# RTU_LMG_CAN.net
KiCad netlist of a schematic drawn in Altium Designer
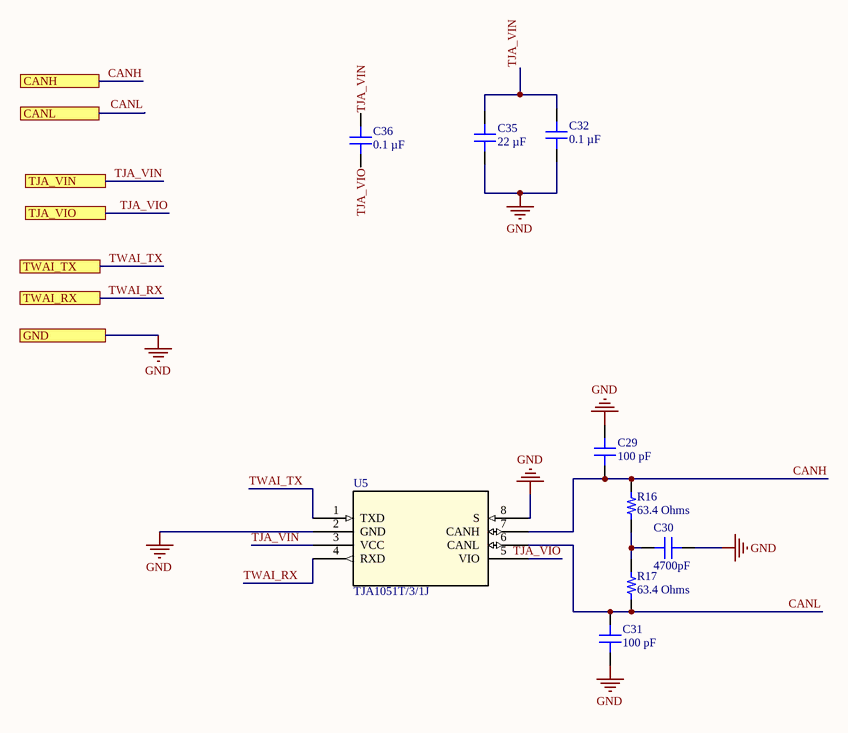
[diagram p0: RTU_LMG_CAN.SchDoc]

(export (version "E")
  (design (tool "Eeschema 10.0.6"))
  (components
    (comp (ref "C29")
      (value "100 pF")
      (footprint "CAP 0402_1005")
      (description "CAP CER 100PF 50V C0G/NP0 0402")
      (fields
        (field (name "PART NUMBER") "500X07N101MV4T")
        (field (name "CAPACITANCE") "100 pF")
        (field (name "MANUFACTURER") "Johanson Dielectrics Inc.")
      )
      (libsource (lib "Celestial Altium Library - altium_library") (part "Capacitor"))
    )
    (comp (ref "C30")
      (value "4700pF")
      (footprint "CAP 0402_1005")
      (description "CAP CER 4700PF 50V X7R 0402")
      (fields
        (field (name "PART NUMBER") "04025C472KAT2A")
        (field (name "CAPACITANCE") "4700pF")
        (field (name "MANUFACTURER") "AVX Corporation")
      )
      (libsource (lib "Celestial Altium Library - altium_library") (part "Capacitor"))
    )
    (comp (ref "C31")
      (value "100 pF")
      (footprint "CAP 0402_1005")
      (description "CAP CER 100PF 50V C0G/NP0 0402")
      (fields
        (field (name "PART NUMBER") "500X07N101MV4T")
        (field (name "CAPACITANCE") "100 pF")
        (field (name "MANUFACTURER") "Johanson Dielectrics Inc.")
      )
      (libsource (lib "Celestial Altium Library - altium_library") (part "Capacitor"))
    )
    (comp (ref "C32")
      (value "0.1 µF")
      (footprint "CAP 0402_1005")
      (description "CAP CER 0.1UF 50V X5R 0402")
      (fields
        (field (name "PART NUMBER") "CGA2B3X5R1H104M050BB")
        (field (name "CAPACITANCE") "0.1 µF")
        (field (name "MANUFACTURER") "TDK Corporation")
      )
      (libsource (lib "Celestial Altium Library - altium_library") (part "Capacitor"))
    )
    (comp (ref "C35")
      (value "22 µF")
      (footprint "CAP 0805_2012")
      (description "CAP CER 22UF 16V X5R 0805")
      (fields
        (field (name "PART NUMBER") "CL21A226MOCLRNC")
        (field (name "MANUFACTURER") "Samsung Electro-Mechanics")
      )
      (libsource (lib "Celestial Altium Library - altium_library") (part "Capacitor"))
    )
    (comp (ref "C36")
      (value "0.1 µF")
      (footprint "CAP 0402_1005")
      (description "CAP CER 0.1UF 50V X5R 0402")
      (fields
        (field (name "PART NUMBER") "CGA2B3X5R1H104M050BB")
        (field (name "CAPACITANCE") "0.1 µF")
        (field (name "MANUFACTURER") "TDK Corporation")
      )
      (libsource (lib "Celestial Altium Library - altium_library") (part "Capacitor"))
    )
    (comp (ref "R16")
      (value "63.4 Ohms")
      (footprint "RES 0805_2012")
      (description "RES SMD 63.4 OHM 1% 1/8W 0805")
      (fields
        (field (name "PART NUMBER") "ERJ-6ENF63R4V")
        (field (name "MANUFACTURER") "Panasonic Electronic Components")
      )
      (libsource (lib "Celestial Altium Library - altium_library") (part "Resistor"))
    )
    (comp (ref "R17")
      (value "63.4 Ohms")
      (footprint "RES 0805_2012")
      (description "RES SMD 63.4 OHM 1% 1/8W 0805")
      (fields
        (field (name "PART NUMBER") "ERJ-6ENF63R4V")
        (field (name "MANUFACTURER") "Panasonic Electronic Components")
      )
      (libsource (lib "Celestial Altium Library - altium_library") (part "Resistor"))
    )
    (comp (ref "U5")
      (value "TJA1051T/3/1J")
      (footprint "SO8_SOT96-1_NXP")
      (description "Description")
      (fields (field (name "COPYRIGHT") "Copyright (C) 2025 Ultra Librarian. All rights reserved."))
      (libsource (lib "TJA1051T31J") (part "TJA1051T31J"))
    )
  )
  (nets
    (net (code "1") (name "/CANH") (class "Default")
      (node (ref "C29") (pin "1") (pinfunction "1_1") (pintype "passive"))
      (node (ref "R16") (pin "2") (pinfunction "2_2") (pintype "passive"))
      (node (ref "U5") (pin "7") (pinfunction "CANH_7") (pintype "bidirectional"))
    )
    (net (code "2") (name "/CANL") (class "Default")
      (node (ref "C31") (pin "2") (pinfunction "2_2") (pintype "passive"))
      (node (ref "R17") (pin "1") (pinfunction "1_1") (pintype "passive"))
      (node (ref "U5") (pin "6") (pinfunction "CANL_6") (pintype "bidirectional"))
    )
    (net (code "3") (name "/TJA_VIN") (class "Default")
      (node (ref "C32") (pin "1") (pinfunction "1_1") (pintype "passive"))
      (node (ref "C35") (pin "2") (pinfunction "2_2") (pintype "passive"))
      (node (ref "C36") (pin "1") (pinfunction "1_1") (pintype "passive"))
      (node (ref "U5") (pin "3") (pinfunction "VCC_3") (pintype "power_in"))
    )
    (net (code "4") (name "/TJA_VIO") (class "Default")
      (node (ref "C36") (pin "2") (pinfunction "2_2") (pintype "passive"))
      (node (ref "U5") (pin "5") (pinfunction "VIO_5") (pintype "power_in"))
    )
    (net (code "5") (name "/TWAI_RX") (class "Default")
      (node (ref "U5") (pin "4") (pinfunction "RXD_4") (pintype "output"))
    )
    (net (code "6") (name "/TWAI_TX") (class "Default")
      (node (ref "U5") (pin "1") (pinfunction "TXD_1") (pintype "input"))
    )
    (net (code "7") (name "GND") (class "Default")
      (node (ref "C29") (pin "2") (pinfunction "2_2") (pintype "passive"))
      (node (ref "C30") (pin "2") (pinfunction "2_2") (pintype "passive"))
      (node (ref "C31") (pin "1") (pinfunction "1_1") (pintype "passive"))
      (node (ref "C32") (pin "2") (pinfunction "2_2") (pintype "passive"))
      (node (ref "C35") (pin "1") (pinfunction "1_1") (pintype "passive"))
      (node (ref "U5") (pin "2") (pinfunction "GND_2") (pintype "power_in"))
      (node (ref "U5") (pin "8") (pinfunction "S_8") (pintype "input"))
    )
    (net (code "8") (name "Net-(C30-Pad1)") (class "Default")
      (node (ref "C30") (pin "1") (pinfunction "1_1") (pintype "passive"))
      (node (ref "R16") (pin "1") (pinfunction "1_1") (pintype "passive"))
      (node (ref "R17") (pin "2") (pinfunction "2_2") (pintype "passive"))
    )
  )
)
